# Power.net
KiCad netlist of a schematic drawn in Altium Designer
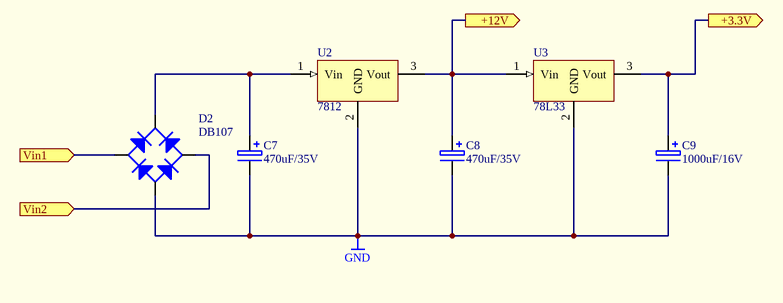
[diagram p0: Power.SchDoc]

(export (version "E")
  (design (tool "Eeschema 10.0.6"))
  (components
    (comp (ref "C7")
      (value "470uF/35V")
      (footprint "EC10x20")
      (description "Electrolytic Capacitor")
      (libsource (lib "*") (part "ELECTRO1"))
    )
    (comp (ref "C8")
      (value "470uF/35V")
      (footprint "EC8x16")
      (description "Electrolytic Capacitor")
      (libsource (lib "*") (part "ELECTRO1"))
    )
    (comp (ref "C9")
      (value "1000uF/16V")
      (footprint "EC6.3x12")
      (description "Electrolytic Capacitor")
      (libsource (lib "*") (part "ELECTRO1"))
    )
    (comp (ref "D2") (value "DB107") (footprint "BRIDGE_PTH") (libsource (lib "*") (part "BRIDGE")))
    (comp (ref "U2") (value "7812") (footprint "TO-220-V") (libsource (lib "*") (part "78XX")))
    (comp (ref "U3") (value "78L33") (footprint "IC_TO-92") (libsource (lib "*") (part "78XX")))
  )
  (nets
    (net (code "1") (name "/+3.3V") (class "Default")
      (node (ref "C9") (pin "1") (pinfunction "1_1") (pintype "passive"))
      (node (ref "U3") (pin "3") (pinfunction "Vout_3") (pintype "power_in"))
    )
    (net (code "2") (name "/+12V") (class "Default")
      (node (ref "C8") (pin "1") (pinfunction "1_1") (pintype "passive"))
      (node (ref "U2") (pin "3") (pinfunction "Vout_3") (pintype "power_in"))
      (node (ref "U3") (pin "1") (pinfunction "Vin_1") (pintype "input"))
    )
    (net (code "3") (name "/Vin1") (class "Default")
      (node (ref "D2") (pin "1") (pinfunction "AC1_1") (pintype "passive"))
    )
    (net (code "4") (name "/Vin2") (class "Default")
      (node (ref "D2") (pin "2") (pinfunction "AC2_2") (pintype "passive"))
    )
    (net (code "5") (name "GND") (class "Default")
      (node (ref "C7") (pin "2") (pinfunction "2_2") (pintype "passive"))
      (node (ref "C8") (pin "2") (pinfunction "2_2") (pintype "passive"))
      (node (ref "C9") (pin "2") (pinfunction "2_2") (pintype "passive"))
      (node (ref "D2") (pin "4") (pinfunction "M_4") (pintype "passive"))
      (node (ref "U2") (pin "2") (pinfunction "GND_2") (pintype "passive"))
      (node (ref "U3") (pin "2") (pinfunction "GND_2") (pintype "passive"))
    )
    (net (code "6") (name "Net-(D2-P)") (class "Default")
      (node (ref "C7") (pin "1") (pinfunction "1_1") (pintype "passive"))
      (node (ref "D2") (pin "3") (pinfunction "P_3") (pintype "passive"))
      (node (ref "U2") (pin "1") (pinfunction "Vin_1") (pintype "input"))
    )
  )
)
